# Milliways.net
KiCad netlist of a schematic drawn in EasyEDA Pro
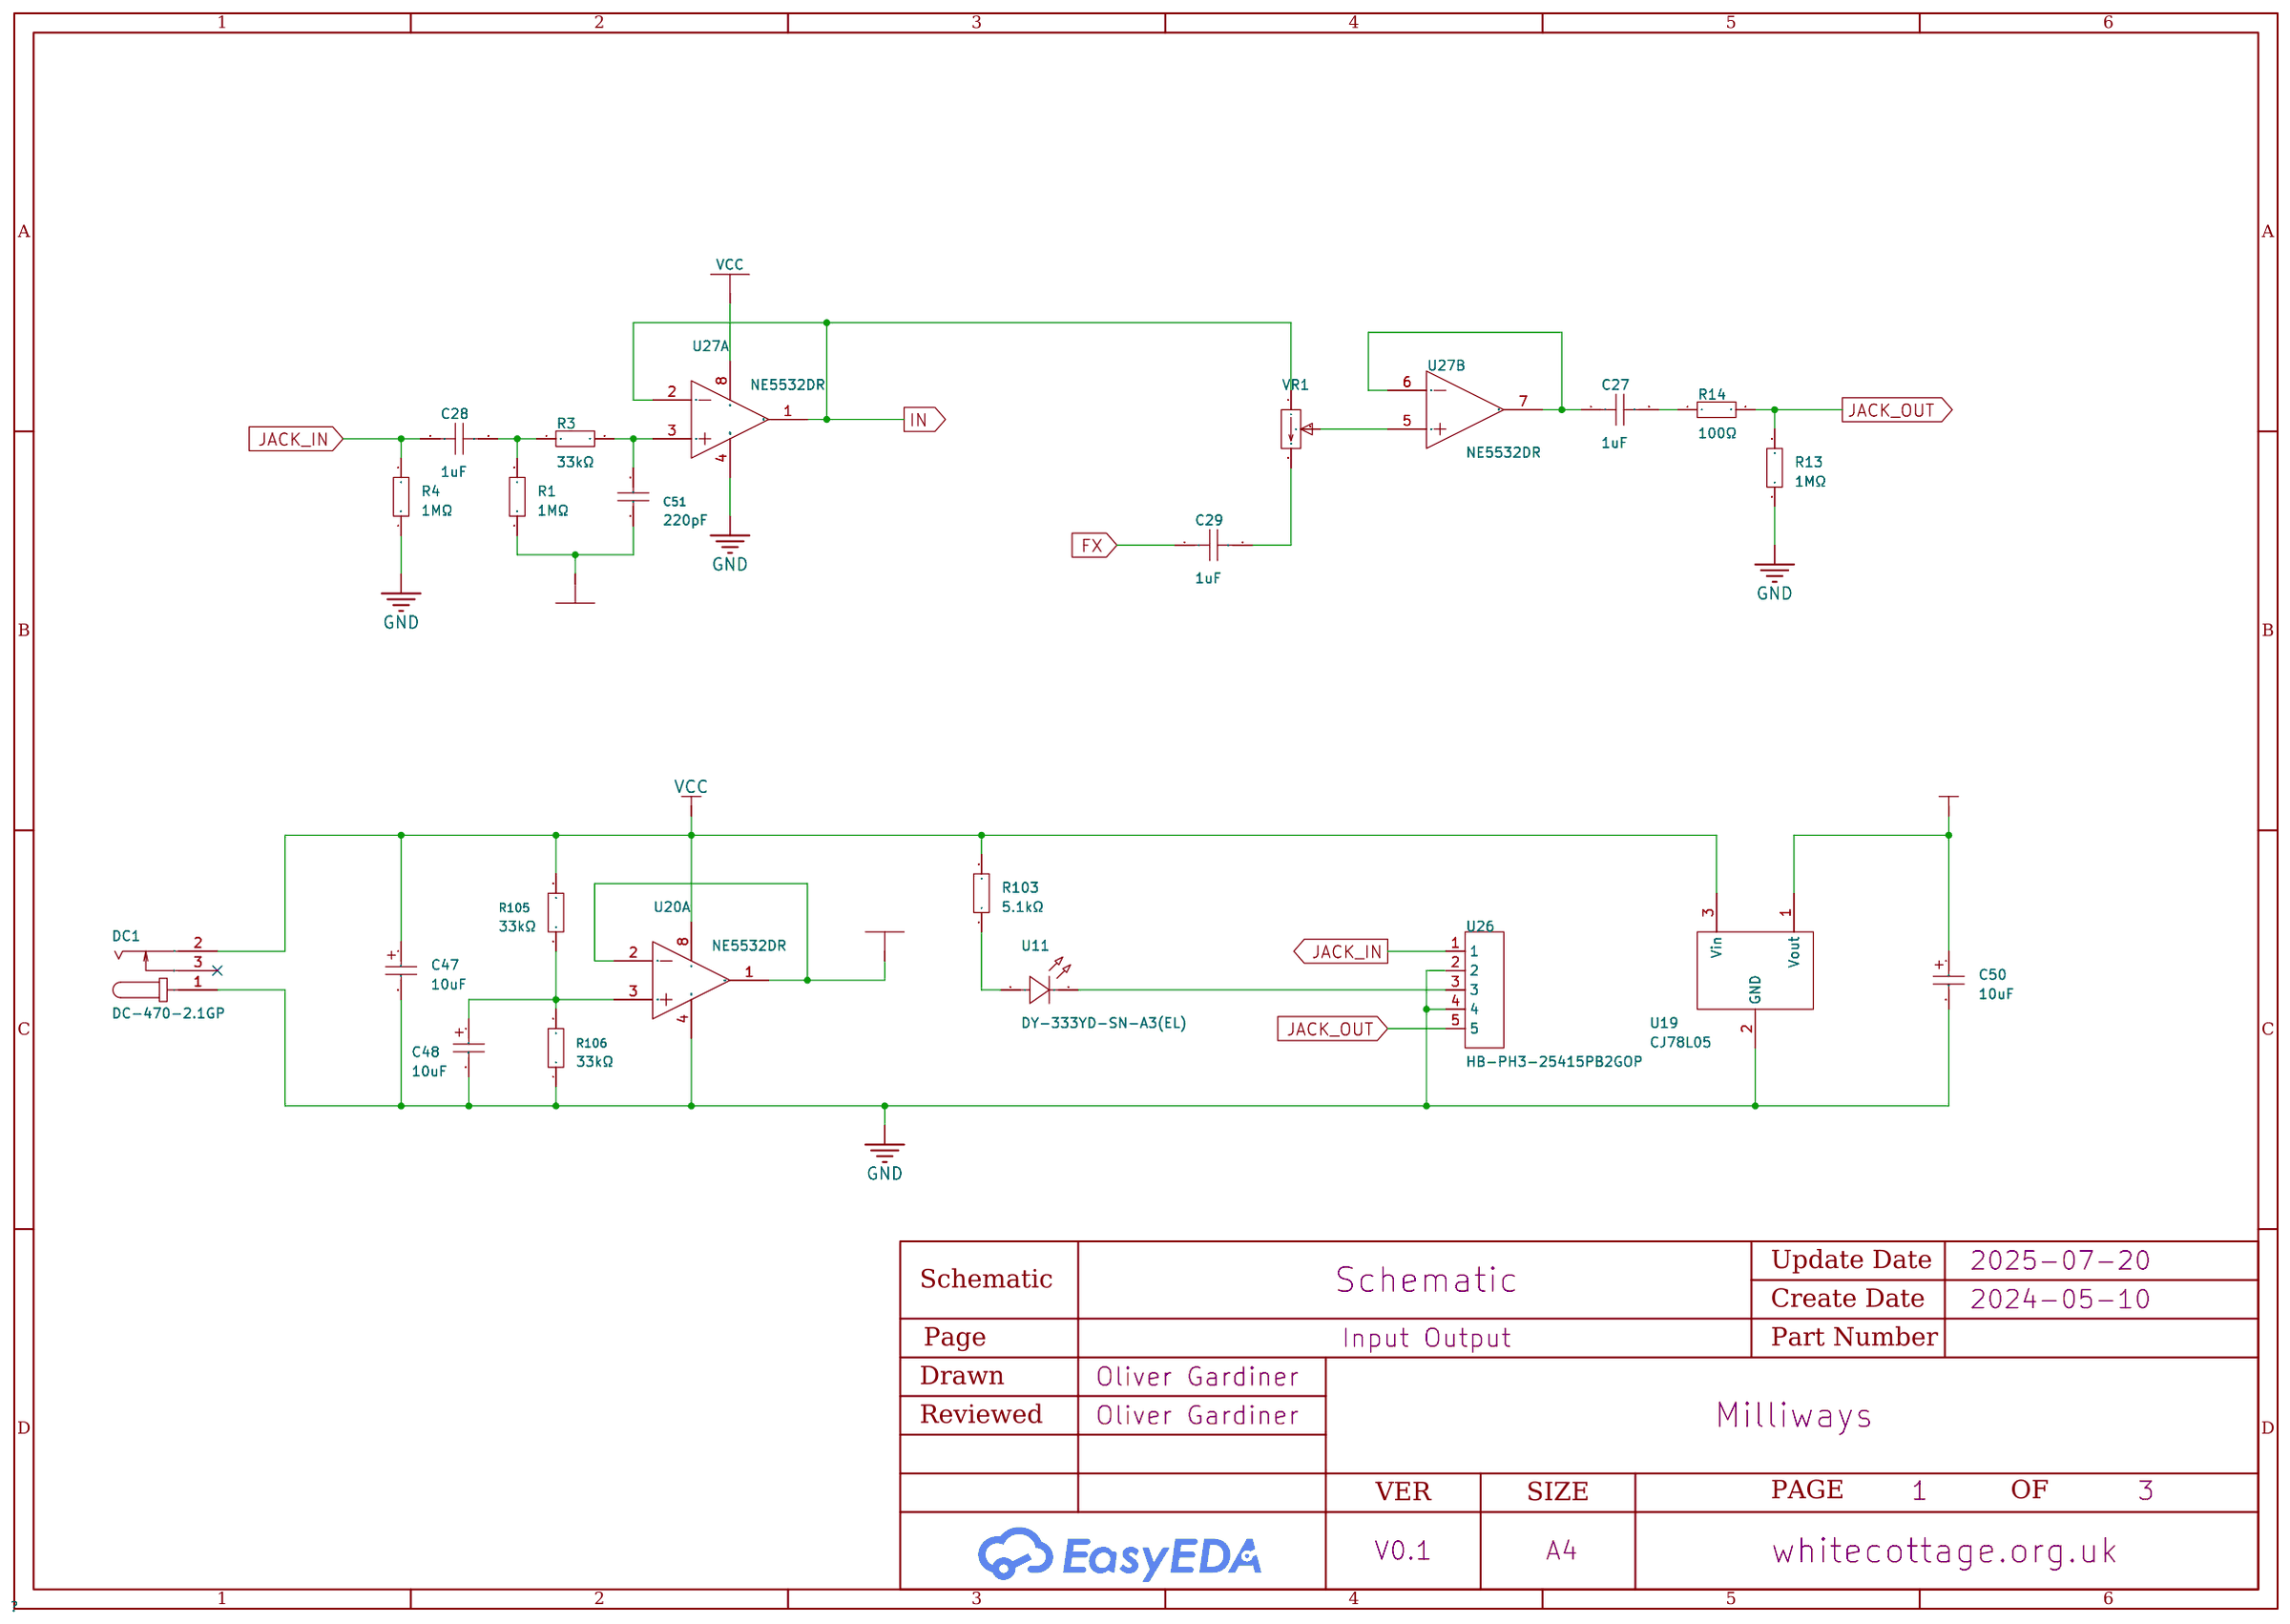
[diagram p0: Input Output]
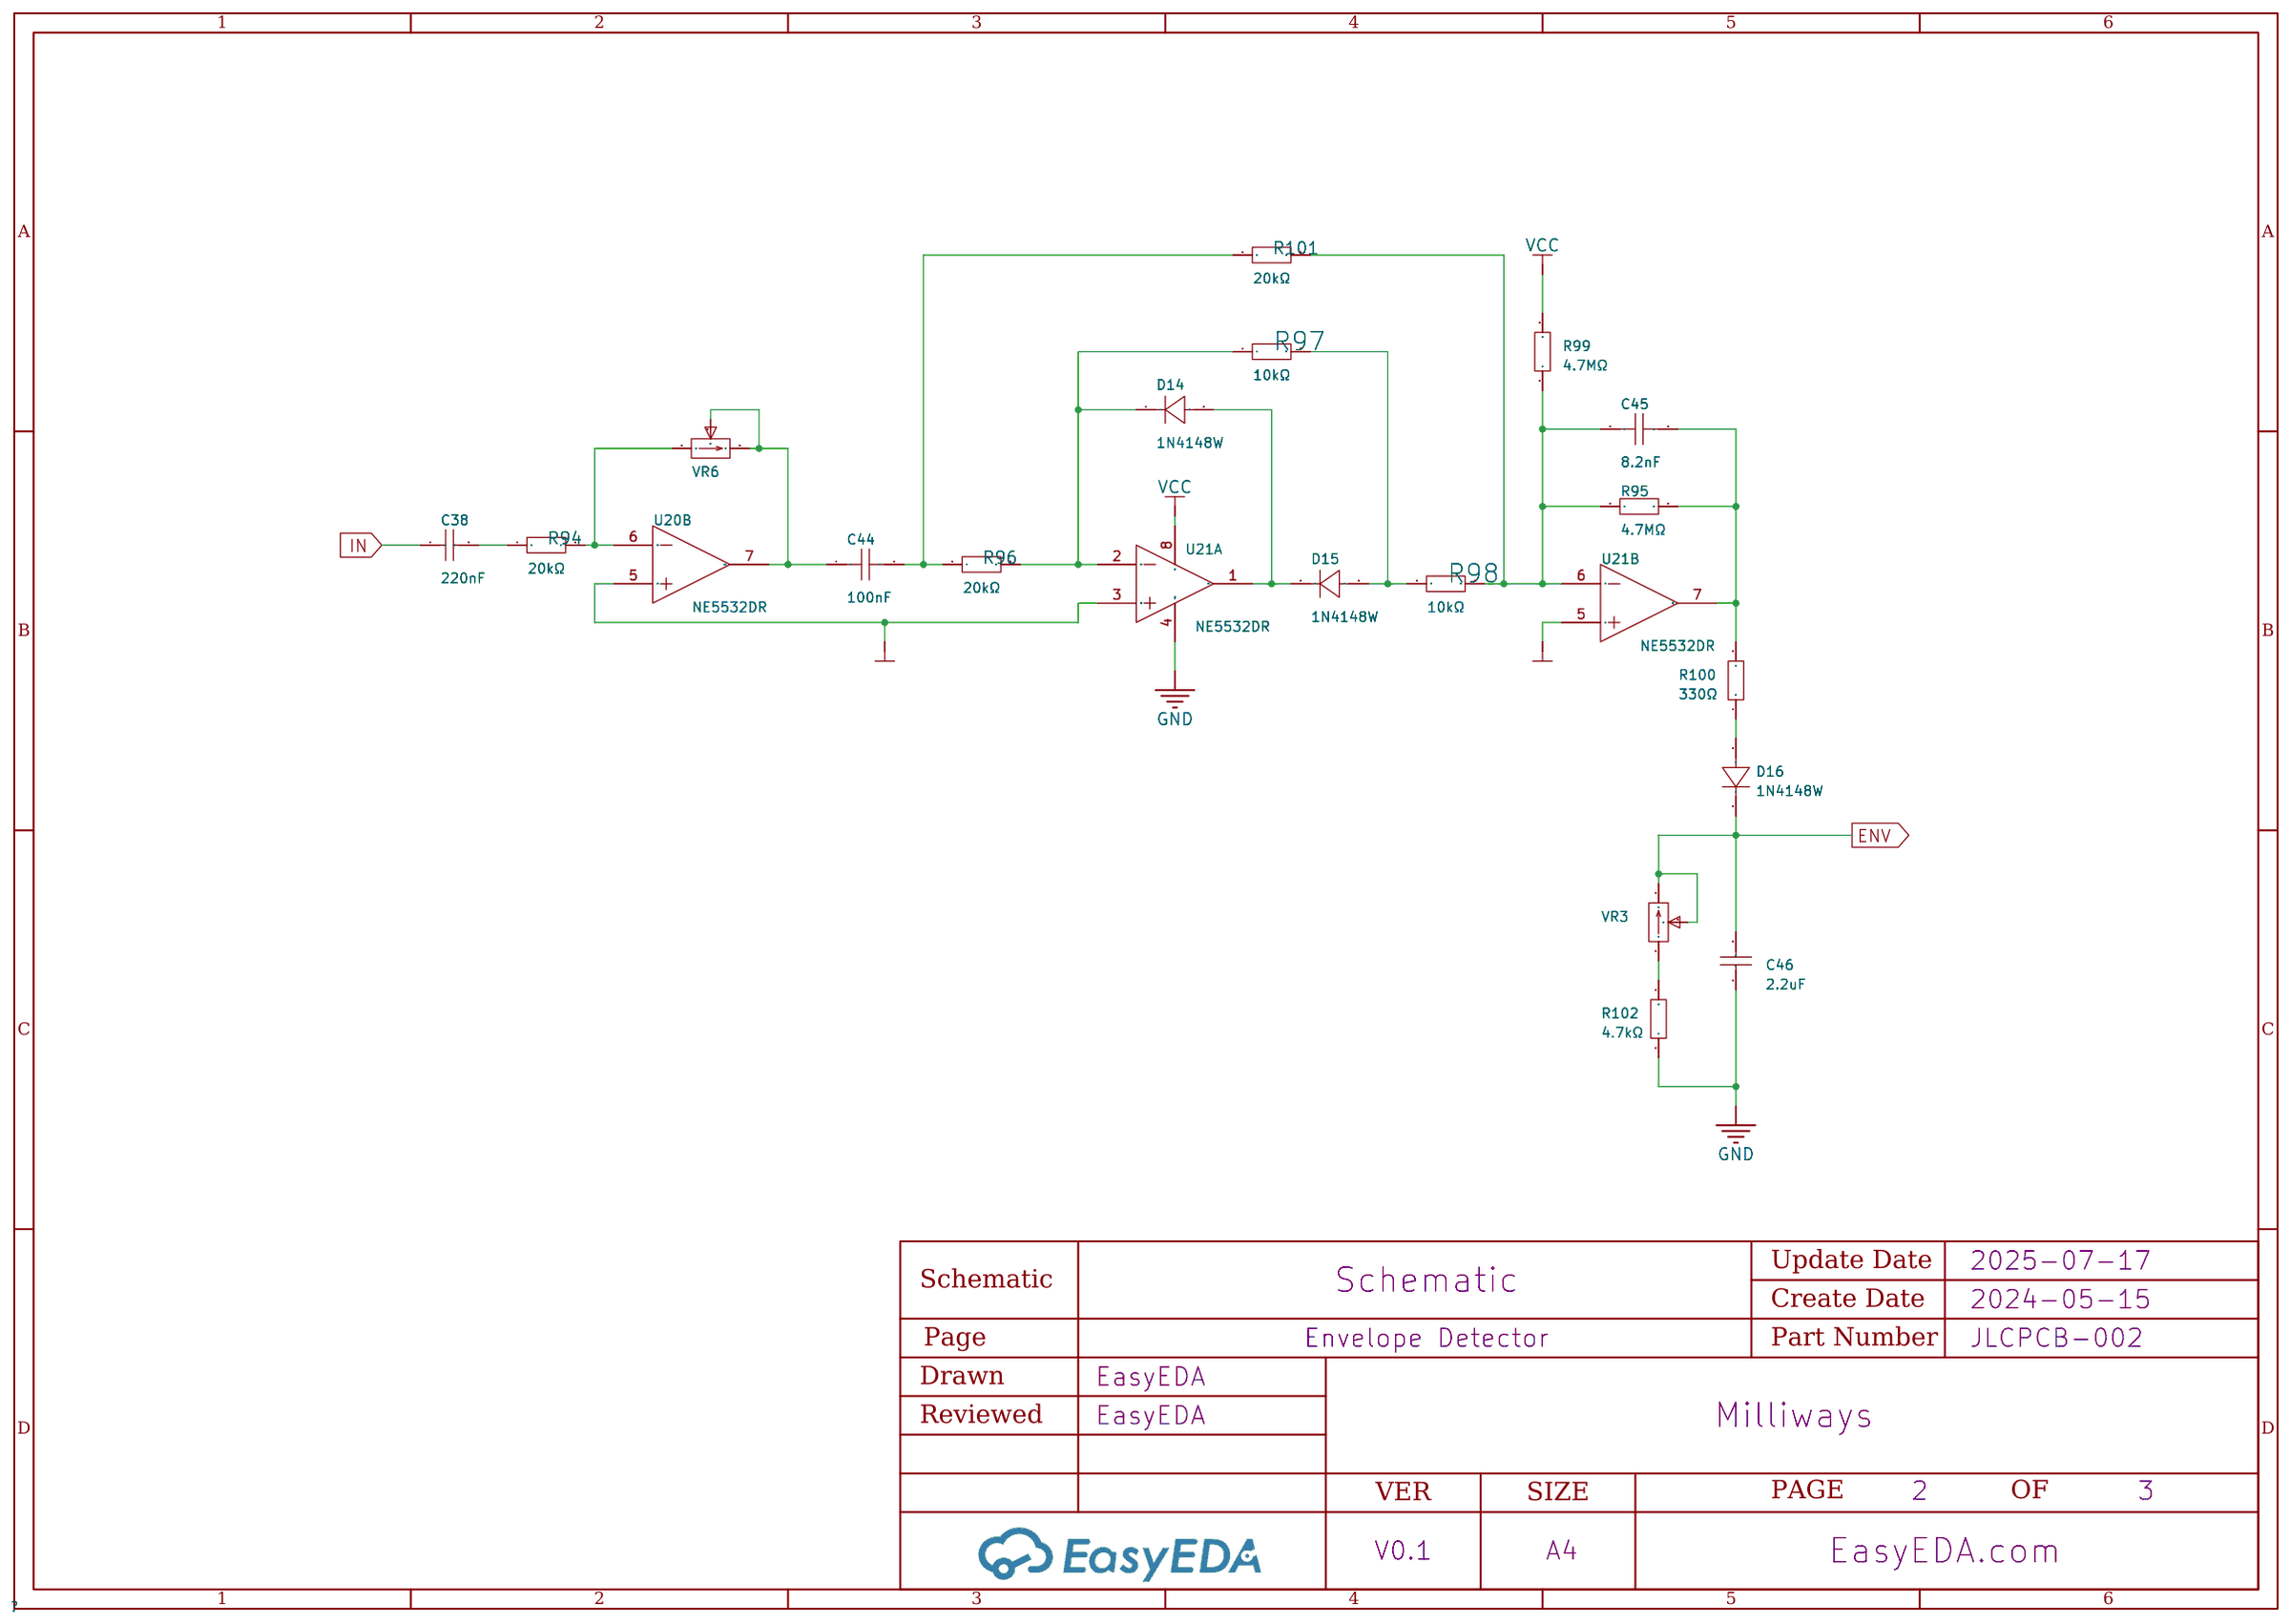
[diagram p1: Envelope Detector]
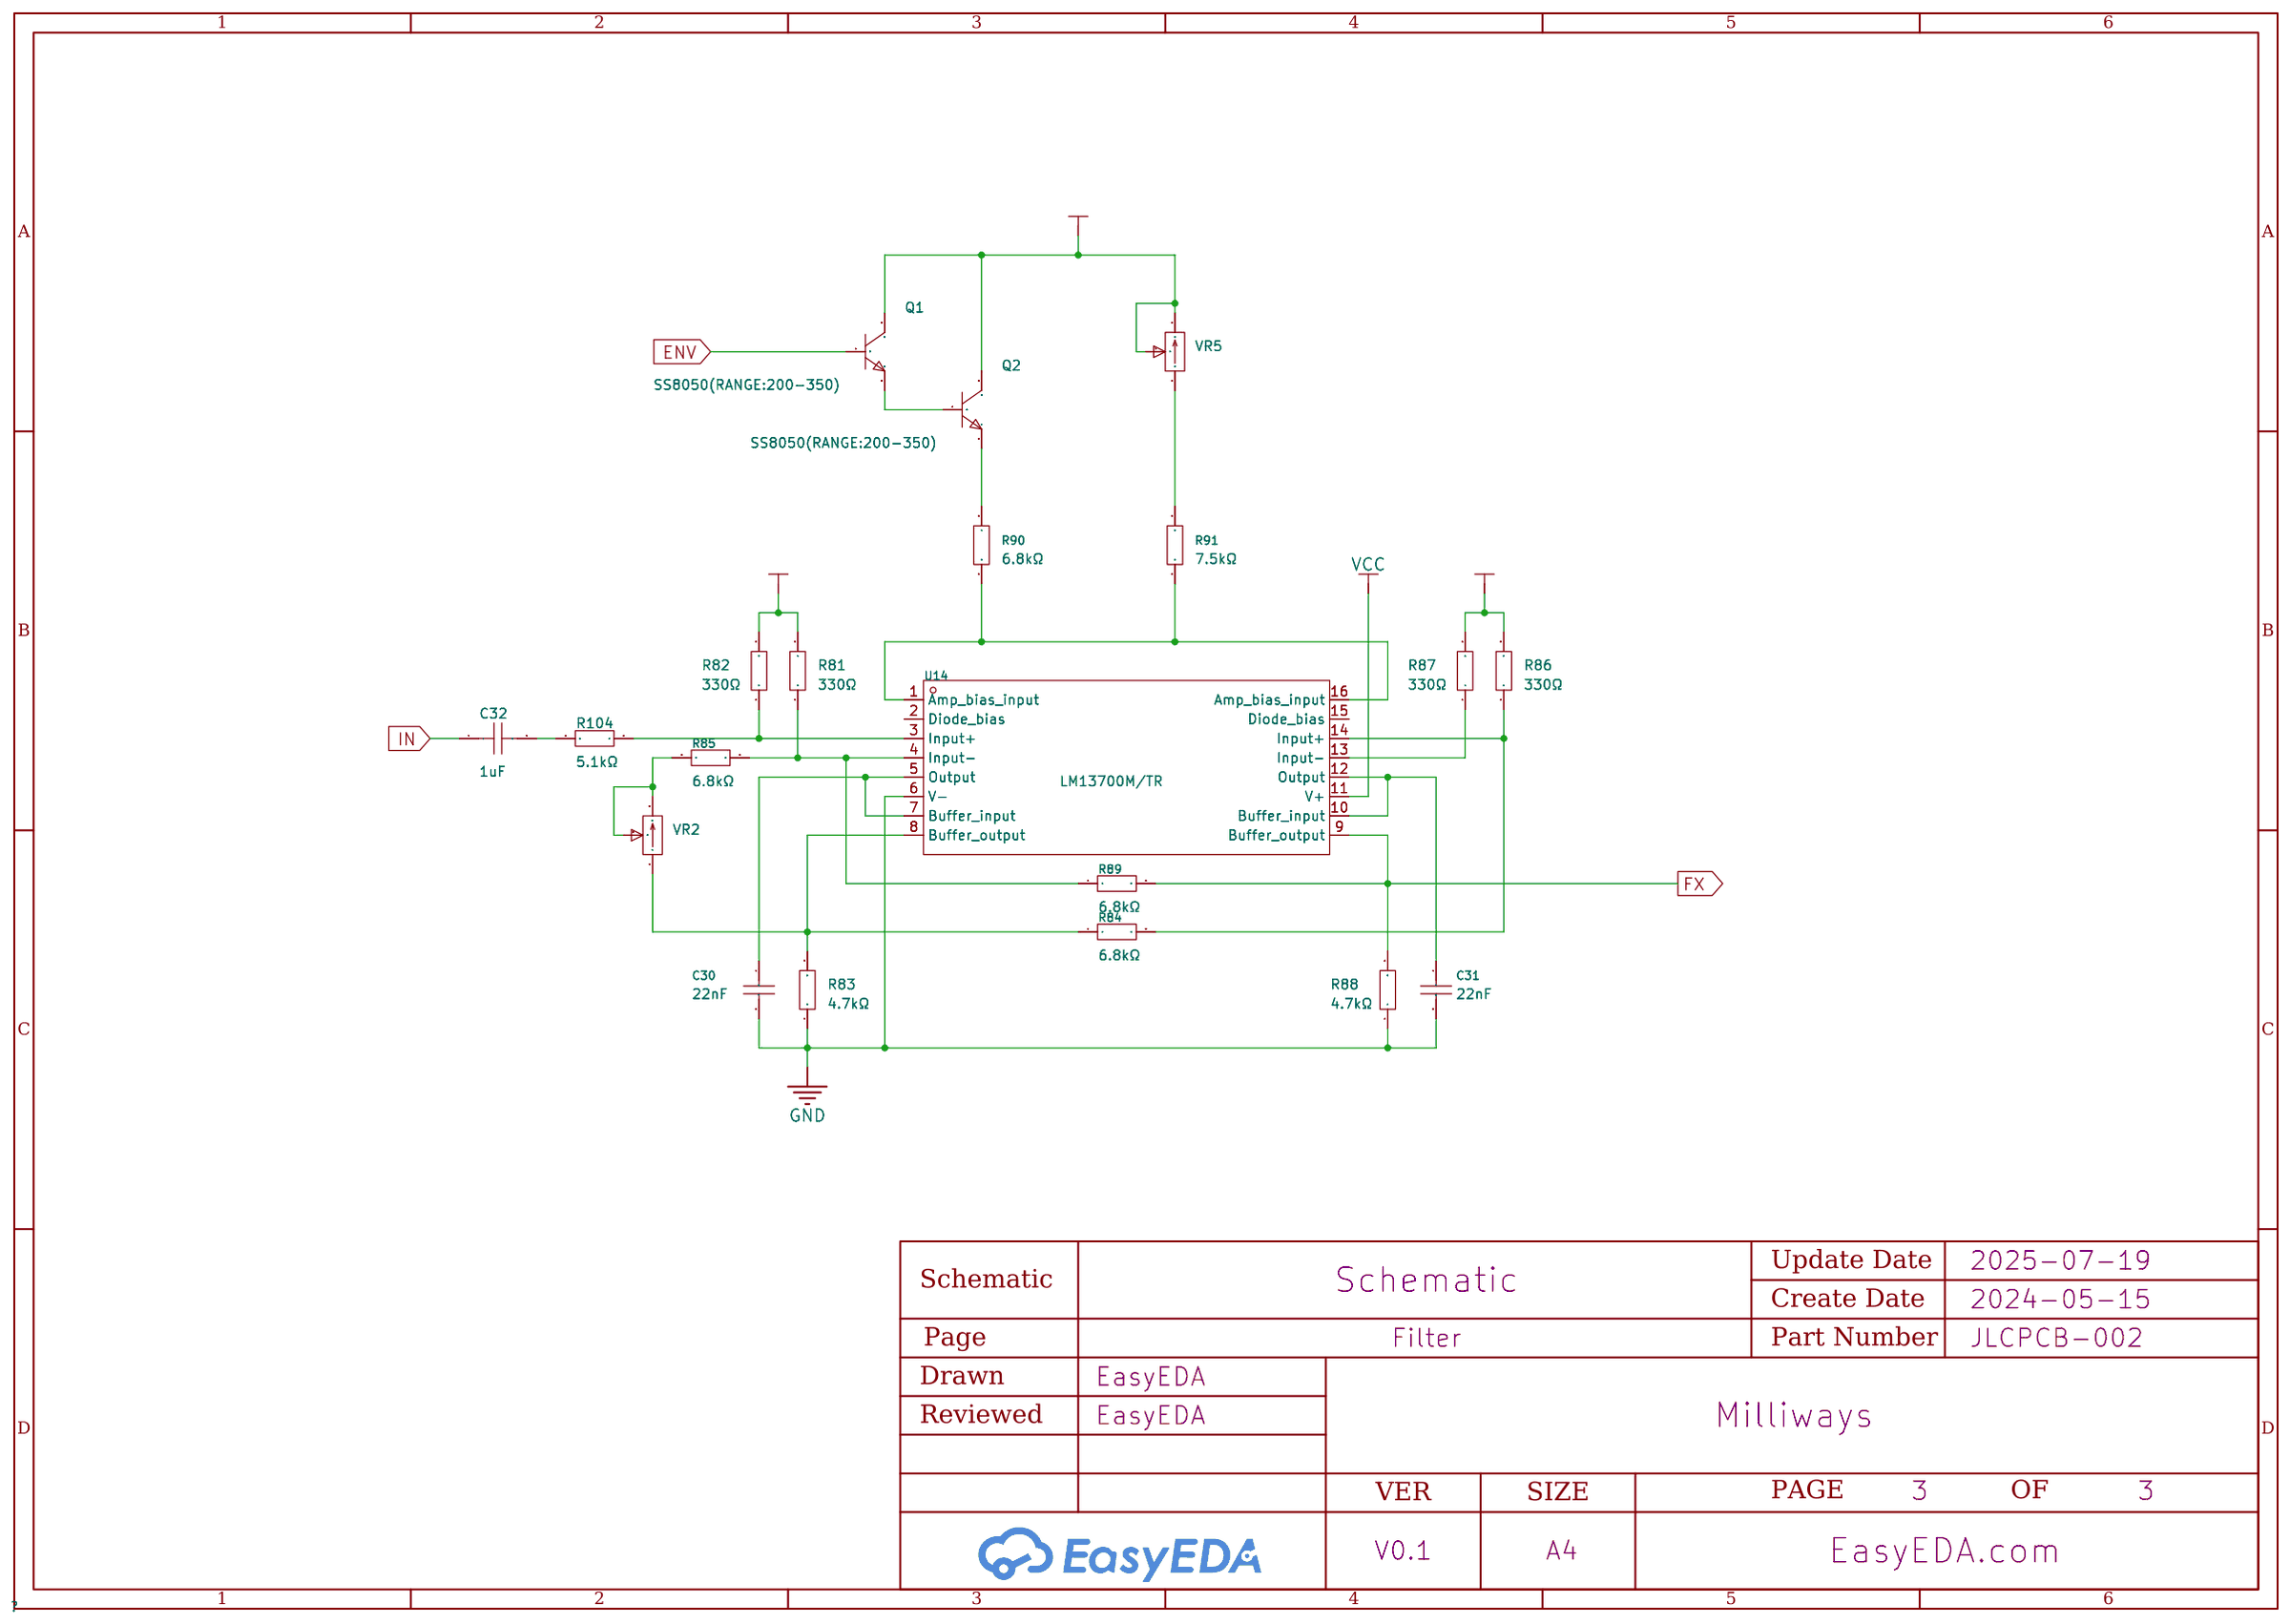
[diagram p2: Filter]

(export (version "E")
  (design (tool "Eeschema 10.0.6"))
  (components
    (comp (ref "C27")
      (value "1uF")
      (fields
        (field (name "Manufacturer Part") "CL10A105KB8NNNC")
        (field (name "Manufacturer") "SAMSUNG(三星)")
      )
      (libsource (lib "easyedapro") (part "CL10A105KB8NNNC"))
    )
    (comp (ref "C28")
      (value "1uF")
      (fields
        (field (name "Manufacturer Part") "CL10A105KB8NNNC")
        (field (name "Manufacturer") "SAMSUNG(三星)")
      )
      (libsource (lib "easyedapro") (part "CL10A105KB8NNNC"))
    )
    (comp (ref "C29")
      (value "1uF")
      (fields
        (field (name "Manufacturer Part") "CL10A105KB8NNNC")
        (field (name "Manufacturer") "SAMSUNG(三星)")
      )
      (libsource (lib "easyedapro") (part "CL10A105KB8NNNC"))
    )
    (comp (ref "C47")
      (value "10uF")
      (footprint "easyedapro:CAP-SMD_L3.2-W1.6-RD-C7171")
      (fields (field (name "Manufacturer Part") "TAJA106K016RNJ") (field (name "Manufacturer") "Kyocera AVX"))
      (libsource (lib "easyedapro") (part "TAJA106K016RNJ"))
    )
    (comp (ref "C48")
      (value "10uF")
      (footprint "easyedapro:CAP-SMD_L3.2-W1.6-RD-C7171")
      (fields (field (name "Manufacturer Part") "TAJA106K016RNJ") (field (name "Manufacturer") "Kyocera AVX"))
      (libsource (lib "easyedapro") (part "TAJA106K016RNJ"))
    )
    (comp (ref "C50")
      (value "10uF")
      (footprint "easyedapro:CAP-SMD_L3.2-W1.6-RD-C7171")
      (fields (field (name "Manufacturer Part") "TAJA106K016RNJ") (field (name "Manufacturer") "Kyocera AVX"))
      (libsource (lib "easyedapro") (part "TAJA106K016RNJ"))
    )
    (comp (ref "C51")
      (value "220pF")
      (footprint "easyedapro:C0603")
      (fields
        (field (name "Manufacturer Part") "CL10B221KB8NNNC")
        (field (name "Manufacturer") "SAMSUNG(三星)")
      )
      (libsource (lib "easyedapro") (part "CL10B221KB8NNNC"))
    )
    (comp (ref "DC1")
      (value "DC-470-2.1GP")
      (footprint "easyedapro:DC-IN-TH_DC-470-2.1GP")
      (fields (field (name "Manufacturer") "GANGYUAN(港源)"))
      (libsource (lib "easyedapro") (part "DC-470-2.1GP"))
    )
    (comp (ref "R1")
      (value "1MΩ")
      (footprint "easyedapro:R0603")
      (fields
        (field (name "Manufacturer Part") "0603WAF1004T5E")
        (field (name "Manufacturer") "UNI-ROYAL(厚声)")
      )
      (libsource (lib "easyedapro") (part "Res"))
    )
    (comp (ref "R3")
      (value "33kΩ")
      (footprint "easyedapro:R0603")
      (fields
        (field (name "Manufacturer Part") "0603WAF3302T5E")
        (field (name "Manufacturer") "UNI-ROYAL(厚声)")
      )
      (libsource (lib "easyedapro") (part "Res"))
    )
    (comp (ref "R4")
      (value "1MΩ")
      (footprint "easyedapro:R0603")
      (fields
        (field (name "Manufacturer Part") "0603WAF1004T5E")
        (field (name "Manufacturer") "UNI-ROYAL(厚声)")
      )
      (libsource (lib "easyedapro") (part "Res"))
    )
    (comp (ref "R13")
      (value "1MΩ")
      (footprint "easyedapro:R0603")
      (fields
        (field (name "Manufacturer Part") "0603WAF1004T5E")
        (field (name "Manufacturer") "UNI-ROYAL(厚声)")
      )
      (libsource (lib "easyedapro") (part "Res"))
    )
    (comp (ref "R14")
      (value "100Ω")
      (footprint "easyedapro:R0603")
      (fields
        (field (name "Manufacturer Part") "0603WAF1000T5E")
        (field (name "Manufacturer") "UNI-ROYAL(厚声)")
      )
      (libsource (lib "easyedapro") (part "Res"))
    )
    (comp (ref "R103")
      (value "5.1kΩ")
      (footprint "easyedapro:R0603")
      (fields
        (field (name "Manufacturer Part") "0603WAF5101T5E")
        (field (name "Manufacturer") "UNI-ROYAL(厚声)")
      )
      (libsource (lib "easyedapro") (part "0603WAF5101T5E"))
    )
    (comp (ref "R105")
      (value "33kΩ")
      (footprint "easyedapro:R0603")
      (fields
        (field (name "Manufacturer Part") "0603WAF3302T5E")
        (field (name "Manufacturer") "UNI-ROYAL(厚声)")
      )
      (libsource (lib "easyedapro") (part "0603WAF3302T5E"))
    )
    (comp (ref "R106")
      (value "33kΩ")
      (footprint "easyedapro:R0603")
      (fields
        (field (name "Manufacturer Part") "0603WAF3302T5E")
        (field (name "Manufacturer") "UNI-ROYAL(厚声)")
      )
      (libsource (lib "easyedapro") (part "0603WAF3302T5E"))
    )
    (comp (ref "U11")
      (value "DY-333YD-SN-A3(EL)")
      (footprint "easyedapro:LED-TH_BD5.0-P2.54-FD-1")
      (fields (field (name "Manufacturer") "TONYU(东裕)"))
      (libsource (lib "easyedapro") (part "DY-333YD-SN-A3(EL)"))
    )
    (comp (ref "U19")
      (value "CJ78L05")
      (footprint "easyedapro:SOT-89-3_L4.5-W2.5-P1.50-LS4.2-BR")
      (fields (field (name "Manufacturer") "CJ(江苏长电/长晶)"))
      (libsource (lib "easyedapro") (part "CJ78L05"))
    )
    (comp (ref "U20")
      (value "NE5532DR")
      (footprint "easyedapro:SOIC-8_L4.9-W3.9-P1.27-LS6.0-BL")
      (fields (field (name "Manufacturer") "TI(德州仪器)"))
      (libsource (lib "easyedapro") (part "NE5532DR"))
    )
    (comp (ref "U26")
      (value "HB-PH3-25415PB2GOP")
      (footprint "easyedapro:HDR-TH_5P-P2.54-V-M")
      (fields (field (name "Manufacturer") "HANBO(汉博)"))
      (libsource (lib "easyedapro") (part "HB-PH3-25415PB2GOP"))
    )
    (comp (ref "U27")
      (value "NE5532DR")
      (footprint "easyedapro:SOIC-8_L4.9-W3.9-P1.27-LS6.0-BL")
      (fields (field (name "Manufacturer") "TI(德州仪器)"))
      (libsource (lib "easyedapro") (part "NE5532DR"))
    )
    (comp (ref "VR1")
      (value "~")
      (footprint "easyedapro:RD901F")
      (libsource (lib "easyedapro") (part "RD901F"))
    )
    (comp (ref "C38")
      (value "220nF")
      (footprint "easyedapro:C0603")
      (fields
        (field (name "Manufacturer Part") "CL10B224KA8NNNC")
        (field (name "Manufacturer") "SAMSUNG(三星)")
      )
      (libsource (lib "easyedapro") (part "CL10B224KA8NNNC"))
    )
    (comp (ref "C44")
      (value "100nF")
      (footprint "easyedapro:C0603")
      (fields
        (field (name "Manufacturer Part") "CC0603KRX7R9BB104")
        (field (name "Manufacturer") "YAGEO(国巨)")
      )
      (libsource (lib "easyedapro") (part "CC0603KRX7R9BB104"))
    )
    (comp (ref "C45")
      (value "8.2nF")
      (footprint "easyedapro:C0603")
      (description "Capacitance:8.2nF Tolerance:±10% Tolerance:±10% Voltage Rating:50V Temperature Coefficient:X7R")
      (fields (field (name "Manufacturer Part") "0603B822K500NT") (field (name "Manufacturer") "FH(风华)"))
      (libsource (lib "easyedapro") (part "0603B822K500NT"))
    )
    (comp (ref "C46")
      (value "2.2uF")
      (footprint "easyedapro:C0603")
      (fields
        (field (name "Manufacturer Part") "CL10A225KO8NNNC")
        (field (name "Manufacturer") "SAMSUNG(三星)")
      )
      (libsource (lib "easyedapro") (part "CL10A225KO8NNNC"))
    )
    (comp (ref "D14")
      (value "1N4148W")
      (fields (field (name "Manufacturer") "ST(先科)"))
      (libsource (lib "easyedapro") (part "d_1n4007"))
    )
    (comp (ref "D15")
      (value "1N4148W")
      (fields (field (name "Manufacturer") "ST(先科)"))
      (libsource (lib "easyedapro") (part "d_1n4007"))
    )
    (comp (ref "D16")
      (value "1N4148W")
      (fields (field (name "Manufacturer") "ST(先科)"))
      (libsource (lib "easyedapro") (part "d_1n4007"))
    )
    (comp (ref "R94")
      (value "20kΩ")
      (footprint "easyedapro:R0603")
      (fields
        (field (name "Manufacturer Part") "0603WAF2002T5E")
        (field (name "Manufacturer") "UNI-ROYAL(厚声)")
      )
      (libsource (lib "easyedapro") (part "0603WAF2002T5E"))
    )
    (comp (ref "R95")
      (value "4.7MΩ")
      (footprint "easyedapro:R0603")
      (fields
        (field (name "Manufacturer Part") "0603WAF4704T5E")
        (field (name "Manufacturer") "UNI-ROYAL(厚声)")
      )
      (libsource (lib "easyedapro") (part "0603WAF4704T5E"))
    )
    (comp (ref "R96")
      (value "20kΩ")
      (footprint "easyedapro:R0603")
      (fields
        (field (name "Manufacturer Part") "0603WAF2002T5E")
        (field (name "Manufacturer") "UNI-ROYAL(厚声)")
      )
      (libsource (lib "easyedapro") (part "0603WAF2002T5E"))
    )
    (comp (ref "R97")
      (value "10kΩ")
      (footprint "easyedapro:R0603")
      (fields
        (field (name "Manufacturer Part") "0603WAF1002T5E")
        (field (name "Manufacturer") "UNI-ROYAL(厚声)")
      )
      (libsource (lib "easyedapro") (part "0603WAF1002T5E"))
    )
    (comp (ref "R98")
      (value "10kΩ")
      (footprint "easyedapro:R0603")
      (fields
        (field (name "Manufacturer Part") "0603WAF1002T5E")
        (field (name "Manufacturer") "UNI-ROYAL(厚声)")
      )
      (libsource (lib "easyedapro") (part "0603WAF1002T5E"))
    )
    (comp (ref "R99")
      (value "4.7MΩ")
      (footprint "easyedapro:R0603")
      (fields
        (field (name "Manufacturer Part") "0603WAF4704T5E")
        (field (name "Manufacturer") "UNI-ROYAL(厚声)")
      )
      (libsource (lib "easyedapro") (part "0603WAF4704T5E"))
    )
    (comp (ref "R100")
      (value "330Ω")
      (footprint "easyedapro:R0603")
      (fields
        (field (name "Manufacturer Part") "0603WAF3300T5E")
        (field (name "Manufacturer") "UNI-ROYAL(厚声)")
      )
      (libsource (lib "easyedapro") (part "0603WAF3300T5E"))
    )
    (comp (ref "R101")
      (value "20kΩ")
      (footprint "easyedapro:R0603")
      (fields
        (field (name "Manufacturer Part") "0603WAF2002T5E")
        (field (name "Manufacturer") "UNI-ROYAL(厚声)")
      )
      (libsource (lib "easyedapro") (part "0603WAF2002T5E"))
    )
    (comp (ref "R102")
      (value "4.7kΩ")
      (footprint "easyedapro:R0603")
      (fields
        (field (name "Manufacturer Part") "0603WAF4701T5E")
        (field (name "Manufacturer") "UNI-ROYAL(厚声)")
      )
      (libsource (lib "easyedapro") (part "0603WAF4701T5E"))
    )
    (comp (ref "U21")
      (value "NE5532DR")
      (footprint "easyedapro:SOIC-8_L4.9-W3.9-P1.27-LS6.0-BL")
      (fields (field (name "Manufacturer") "TI(德州仪器)"))
      (libsource (lib "easyedapro") (part "NE5532DR"))
    )
    (comp (ref "VR3")
      (value "~")
      (footprint "easyedapro:RD901F")
      (libsource (lib "easyedapro") (part "RD901F"))
    )
    (comp (ref "VR6")
      (value "~")
      (footprint "easyedapro:RD901F")
      (libsource (lib "easyedapro") (part "RD901F"))
    )
    (comp (ref "C30")
      (value "22nF")
      (footprint "easyedapro:C0603")
      (fields
        (field (name "Manufacturer Part") "CL10B223KB8NNNC")
        (field (name "Manufacturer") "SAMSUNG(三星)")
      )
      (libsource (lib "easyedapro") (part "CL10B223KB8NNNC"))
    )
    (comp (ref "C31")
      (value "22nF")
      (footprint "easyedapro:C0603")
      (fields
        (field (name "Manufacturer Part") "CL10B223KB8NNNC")
        (field (name "Manufacturer") "SAMSUNG(三星)")
      )
      (libsource (lib "easyedapro") (part "CL10B223KB8NNNC"))
    )
    (comp (ref "C32")
      (value "1uF")
      (footprint "easyedapro:C0603")
      (fields
        (field (name "Manufacturer Part") "CL10A105KB8NNNC")
        (field (name "Manufacturer") "SAMSUNG(三星)")
      )
      (libsource (lib "easyedapro") (part "CL10A105KB8NNNC"))
    )
    (comp (ref "Q1")
      (value "SS8050(RANGE:200-350)")
      (footprint "easyedapro:SOT-23-3_L2.9-W1.3-P1.90-LS2.4-BR")
      (fields (field (name "Manufacturer") "CJ(江苏长电/长晶)"))
      (libsource (lib "easyedapro") (part "SS8050_C2150"))
    )
    (comp (ref "Q2")
      (value "SS8050(RANGE:200-350)")
      (footprint "easyedapro:SOT-23-3_L2.9-W1.3-P1.90-LS2.4-BR")
      (fields (field (name "Manufacturer") "CJ(江苏长电/长晶)"))
      (libsource (lib "easyedapro") (part "SS8050_C2150"))
    )
    (comp (ref "R81")
      (value "330Ω")
      (footprint "easyedapro:R0603")
      (fields
        (field (name "Manufacturer Part") "0603WAF3300T5E")
        (field (name "Manufacturer") "UNI-ROYAL(厚声)")
      )
      (libsource (lib "easyedapro") (part "0603WAF3300T5E"))
    )
    (comp (ref "R82")
      (value "330Ω")
      (footprint "easyedapro:R0603")
      (fields
        (field (name "Manufacturer Part") "0603WAF3300T5E")
        (field (name "Manufacturer") "UNI-ROYAL(厚声)")
      )
      (libsource (lib "easyedapro") (part "0603WAF3300T5E"))
    )
    (comp (ref "R83")
      (value "4.7kΩ")
      (footprint "easyedapro:R0603")
      (fields
        (field (name "Manufacturer Part") "0603WAF4701T5E")
        (field (name "Manufacturer") "UNI-ROYAL(厚声)")
      )
      (libsource (lib "easyedapro") (part "0603WAF4701T5E"))
    )
    (comp (ref "R84")
      (value "6.8kΩ")
      (footprint "easyedapro:R0603")
      (fields
        (field (name "Manufacturer Part") "0603WAF6801T5E")
        (field (name "Manufacturer") "UNI-ROYAL(厚声)")
      )
      (libsource (lib "easyedapro") (part "0603WAF6801T5E"))
    )
    (comp (ref "R85")
      (value "6.8kΩ")
      (footprint "easyedapro:R0603")
      (fields
        (field (name "Manufacturer Part") "0603WAF6801T5E")
        (field (name "Manufacturer") "UNI-ROYAL(厚声)")
      )
      (libsource (lib "easyedapro") (part "0603WAF6801T5E"))
    )
    (comp (ref "R86")
      (value "330Ω")
      (footprint "easyedapro:R0603")
      (fields
        (field (name "Manufacturer Part") "0603WAF3300T5E")
        (field (name "Manufacturer") "UNI-ROYAL(厚声)")
      )
      (libsource (lib "easyedapro") (part "0603WAF3300T5E"))
    )
    (comp (ref "R87")
      (value "330Ω")
      (footprint "easyedapro:R0603")
      (fields
        (field (name "Manufacturer Part") "0603WAF3300T5E")
        (field (name "Manufacturer") "UNI-ROYAL(厚声)")
      )
      (libsource (lib "easyedapro") (part "0603WAF3300T5E"))
    )
    (comp (ref "R88")
      (value "4.7kΩ")
      (footprint "easyedapro:R0603")
      (fields
        (field (name "Manufacturer Part") "0603WAF4701T5E")
        (field (name "Manufacturer") "UNI-ROYAL(厚声)")
      )
      (libsource (lib "easyedapro") (part "0603WAF4701T5E"))
    )
    (comp (ref "R89")
      (value "6.8kΩ")
      (footprint "easyedapro:R0603")
      (fields
        (field (name "Manufacturer Part") "0603WAF6801T5E")
        (field (name "Manufacturer") "UNI-ROYAL(厚声)")
      )
      (libsource (lib "easyedapro") (part "0603WAF6801T5E"))
    )
    (comp (ref "R90")
      (value "6.8kΩ")
      (footprint "easyedapro:R0603")
      (fields
        (field (name "Manufacturer Part") "0603WAF6801T5E")
        (field (name "Manufacturer") "UNI-ROYAL(厚声)")
      )
      (libsource (lib "easyedapro") (part "0603WAF6801T5E"))
    )
    (comp (ref "R91")
      (value "7.5kΩ")
      (footprint "easyedapro:R0603")
      (fields
        (field (name "Manufacturer Part") "0603WAF7501T5E")
        (field (name "Manufacturer") "UNI-ROYAL(厚声)")
      )
      (libsource (lib "easyedapro") (part "0603WAF7501T5E"))
    )
    (comp (ref "R104")
      (value "5.1kΩ")
      (footprint "easyedapro:R0603")
      (fields
        (field (name "Manufacturer Part") "0603WAF5101T5E")
        (field (name "Manufacturer") "UNI-ROYAL(厚声)")
      )
      (libsource (lib "easyedapro") (part "0603WAF5101T5E"))
    )
    (comp (ref "U14")
      (value "LM13700M/TR")
      (footprint "easyedapro:SOP-16_L9.9-W3.9-P1.27-LS6.0-BL")
      (fields (field (name "Manufacturer") "HGSEMI(华冠)"))
      (libsource (lib "easyedapro") (part "LM13700M/TR"))
    )
    (comp (ref "VR2")
      (value "~")
      (footprint "easyedapro:RD901F")
      (libsource (lib "easyedapro") (part "RD901F"))
    )
    (comp (ref "VR5")
      (value "~")
      (footprint "easyedapro:RD901F")
      (libsource (lib "easyedapro") (part "RD901F"))
    )
  )
  (nets
    (net (code "1") (name "+5V") (class "Default")
      (node (ref "C50") (pin "1") (pinfunction "1_1") (pintype "input"))
      (node (ref "Q1") (pin "3") (pinfunction "C_3") (pintype "unspecified"))
      (node (ref "Q2") (pin "3") (pinfunction "C_3") (pintype "unspecified"))
      (node (ref "U19") (pin "1") (pinfunction "Vout_1") (pintype "unspecified"))
      (node (ref "VR5") (pin "2") (pinfunction "2_2") (pintype "input"))
      (node (ref "VR5") (pin "3") (pinfunction "3_3") (pintype "input"))
    )
    (net (code "2") (name "ENV") (class "Default")
      (node (ref "C46") (pin "2") (pinfunction "2_2") (pintype "input"))
      (node (ref "D16") (pin "1") (pinfunction "K_1") (pintype "input"))
      (node (ref "Q1") (pin "1") (pinfunction "B_1") (pintype "unspecified"))
      (node (ref "VR3") (pin "2") (pinfunction "2_2") (pintype "input"))
      (node (ref "VR3") (pin "3") (pinfunction "3_3") (pintype "input"))
    )
    (net (code "3") (name "FX") (class "Default")
      (node (ref "C29") (pin "1") (pinfunction "1_1") (pintype "unspecified"))
      (node (ref "R88") (pin "2") (pinfunction "2_2") (pintype "input"))
      (node (ref "R89") (pin "2") (pinfunction "2_2") (pintype "input"))
      (node (ref "U14") (pin "9") (pinfunction "Buffer_output_9") (pintype "input"))
    )
    (net (code "4") (name "GND") (class "Default")
      (node (ref "C30") (pin "2") (pinfunction "2_2") (pintype "input"))
      (node (ref "C31") (pin "2") (pinfunction "2_2") (pintype "input"))
      (node (ref "C46") (pin "1") (pinfunction "1_1") (pintype "input"))
      (node (ref "C47") (pin "2") (pinfunction "2_2") (pintype "input"))
      (node (ref "C48") (pin "2") (pinfunction "2_2") (pintype "input"))
      (node (ref "C50") (pin "2") (pinfunction "2_2") (pintype "input"))
      (node (ref "DC1") (pin "1") (pinfunction "1_1") (pintype "unspecified"))
      (node (ref "R102") (pin "1") (pinfunction "1_1") (pintype "input"))
      (node (ref "R106") (pin "1") (pinfunction "1_1") (pintype "input"))
      (node (ref "R13") (pin "1") (pinfunction "1_1") (pintype "input"))
      (node (ref "R4") (pin "1") (pinfunction "1_1") (pintype "input"))
      (node (ref "R83") (pin "1") (pinfunction "1_1") (pintype "input"))
      (node (ref "R88") (pin "1") (pinfunction "1_1") (pintype "input"))
      (node (ref "U14") (pin "6") (pinfunction "V-_6") (pintype "input"))
      (node (ref "U19") (pin "2") (pinfunction "GND_2") (pintype "unspecified"))
      (node (ref "U20") (pin "4") (pinfunction "VCC-/GND_4") (pintype "unspecified"))
      (node (ref "U21") (pin "4") (pinfunction "VCC-/GND_4") (pintype "unspecified"))
      (node (ref "U26") (pin "2") (pinfunction "2_2") (pintype "unspecified"))
      (node (ref "U26") (pin "4") (pinfunction "4_4") (pintype "unspecified"))
      (node (ref "U27") (pin "4") (pinfunction "VCC-/GND_4") (pintype "unspecified"))
    )
    (net (code "5") (name "IN") (class "Default")
      (node (ref "C32") (pin "1") (pinfunction "1_1") (pintype "unspecified"))
      (node (ref "C38") (pin "1") (pinfunction "1_1") (pintype "input"))
      (node (ref "U27") (pin "1") (pinfunction "OUT1_1") (pintype "output"))
      (node (ref "U27") (pin "2") (pinfunction "IN1-_2") (pintype "unspecified"))
      (node (ref "VR1") (pin "1") (pinfunction "1_1") (pintype "input"))
    )
    (net (code "6") (name "JACK_IN") (class "Default")
      (node (ref "C28") (pin "1") (pinfunction "1_1") (pintype "unspecified"))
      (node (ref "R4") (pin "2") (pinfunction "2_2") (pintype "input"))
      (node (ref "U26") (pin "1") (pinfunction "1_1") (pintype "unspecified"))
    )
    (net (code "7") (name "JACK_OUT") (class "Default")
      (node (ref "R13") (pin "2") (pinfunction "2_2") (pintype "input"))
      (node (ref "R14") (pin "2") (pinfunction "2_2") (pintype "input"))
      (node (ref "U26") (pin "5") (pinfunction "5_5") (pintype "unspecified"))
    )
    (net (code "8") (name "Net-(C27-Pad2)") (class "Default")
      (node (ref "C27") (pin "2") (pinfunction "2_2") (pintype "unspecified"))
      (node (ref "R14") (pin "1") (pinfunction "1_1") (pintype "input"))
    )
    (net (code "9") (name "Net-(C28-Pad2)") (class "Default")
      (node (ref "C28") (pin "2") (pinfunction "2_2") (pintype "unspecified"))
      (node (ref "R1") (pin "2") (pinfunction "2_2") (pintype "input"))
      (node (ref "R3") (pin "1") (pinfunction "1_1") (pintype "input"))
    )
    (net (code "10") (name "Net-(C29-Pad2)") (class "Default")
      (node (ref "C29") (pin "2") (pinfunction "2_2") (pintype "unspecified"))
      (node (ref "VR1") (pin "3") (pinfunction "3_3") (pintype "input"))
    )
    (net (code "11") (name "Net-(C30-Pad1)") (class "Default")
      (node (ref "C30") (pin "1") (pinfunction "1_1") (pintype "input"))
      (node (ref "U14") (pin "5") (pinfunction "Output_5") (pintype "input"))
      (node (ref "U14") (pin "7") (pinfunction "Buffer_input_7") (pintype "input"))
    )
    (net (code "12") (name "Net-(C31-Pad1)") (class "Default")
      (node (ref "C31") (pin "1") (pinfunction "1_1") (pintype "input"))
      (node (ref "U14") (pin "10") (pinfunction "Buffer_input_10") (pintype "input"))
      (node (ref "U14") (pin "12") (pinfunction "Output_12") (pintype "input"))
    )
    (net (code "13") (name "Net-(C32-Pad2)") (class "Default")
      (node (ref "C32") (pin "2") (pinfunction "2_2") (pintype "unspecified"))
      (node (ref "R104") (pin "2") (pinfunction "2_2") (pintype "input"))
    )
    (net (code "14") (name "Net-(C38-Pad2)") (class "Default")
      (node (ref "C38") (pin "2") (pinfunction "2_2") (pintype "input"))
      (node (ref "R94") (pin "1") (pinfunction "1_1") (pintype "input"))
    )
    (net (code "15") (name "Net-(C44-Pad2)") (class "Default")
      (node (ref "C44") (pin "2") (pinfunction "2_2") (pintype "unspecified"))
      (node (ref "R101") (pin "1") (pinfunction "1_1") (pintype "input"))
      (node (ref "R96") (pin "1") (pinfunction "1_1") (pintype "input"))
    )
    (net (code "16") (name "Net-(D14-A)") (class "Default")
      (node (ref "D14") (pin "2") (pinfunction "A_2") (pintype "input"))
      (node (ref "D15") (pin "1") (pinfunction "K_1") (pintype "input"))
      (node (ref "U21") (pin "1") (pinfunction "OUT1_1") (pintype "output"))
    )
    (net (code "17") (name "Net-(D14-K)") (class "Default")
      (node (ref "D14") (pin "1") (pinfunction "K_1") (pintype "input"))
      (node (ref "R96") (pin "2") (pinfunction "2_2") (pintype "input"))
      (node (ref "R97") (pin "1") (pinfunction "1_1") (pintype "input"))
      (node (ref "U21") (pin "2") (pinfunction "IN1-_2") (pintype "unspecified"))
    )
    (net (code "18") (name "Net-(D15-A)") (class "Default")
      (node (ref "D15") (pin "2") (pinfunction "A_2") (pintype "input"))
      (node (ref "R97") (pin "2") (pinfunction "2_2") (pintype "input"))
      (node (ref "R98") (pin "1") (pinfunction "1_1") (pintype "input"))
    )
    (net (code "19") (name "Net-(D16-A)") (class "Default")
      (node (ref "D16") (pin "2") (pinfunction "A_2") (pintype "input"))
      (node (ref "R100") (pin "1") (pinfunction "1_1") (pintype "input"))
    )
    (net (code "20") (name "Net-(Q1-E)") (class "Default")
      (node (ref "Q1") (pin "2") (pinfunction "E_2") (pintype "unspecified"))
      (node (ref "Q2") (pin "1") (pinfunction "B_1") (pintype "unspecified"))
    )
    (net (code "21") (name "Net-(Q2-E)") (class "Default")
      (node (ref "Q2") (pin "2") (pinfunction "E_2") (pintype "unspecified"))
      (node (ref "R90") (pin "2") (pinfunction "2_2") (pintype "input"))
    )
    (net (code "22") (name "Net-(R81-Pad1)") (class "Default")
      (node (ref "R81") (pin "1") (pinfunction "1_1") (pintype "input"))
      (node (ref "R85") (pin "2") (pinfunction "2_2") (pintype "input"))
      (node (ref "R89") (pin "1") (pinfunction "1_1") (pintype "input"))
      (node (ref "U14") (pin "4") (pinfunction "Input-_4") (pintype "input"))
    )
    (net (code "23") (name "Net-(R83-Pad2)") (class "Default")
      (node (ref "R83") (pin "2") (pinfunction "2_2") (pintype "input"))
      (node (ref "R84") (pin "1") (pinfunction "1_1") (pintype "input"))
      (node (ref "U14") (pin "8") (pinfunction "Buffer_output_8") (pintype "input"))
      (node (ref "VR2") (pin "1") (pinfunction "1_1") (pintype "input"))
    )
    (net (code "24") (name "Net-(R84-Pad2)") (class "Default")
      (node (ref "R84") (pin "2") (pinfunction "2_2") (pintype "input"))
      (node (ref "R86") (pin "1") (pinfunction "1_1") (pintype "input"))
      (node (ref "U14") (pin "14") (pinfunction "Input+_14") (pintype "input"))
    )
    (net (code "25") (name "Net-(R85-Pad1)") (class "Default")
      (node (ref "R85") (pin "1") (pinfunction "1_1") (pintype "input"))
      (node (ref "VR2") (pin "2") (pinfunction "2_2") (pintype "input"))
      (node (ref "VR2") (pin "3") (pinfunction "3_3") (pintype "input"))
    )
    (net (code "26") (name "Net-(R87-Pad1)") (class "Default")
      (node (ref "R87") (pin "1") (pinfunction "1_1") (pintype "input"))
      (node (ref "U14") (pin "13") (pinfunction "Input-_13") (pintype "input"))
    )
    (net (code "27") (name "Net-(R90-Pad1)") (class "Default")
      (node (ref "R90") (pin "1") (pinfunction "1_1") (pintype "input"))
      (node (ref "R91") (pin "1") (pinfunction "1_1") (pintype "input"))
      (node (ref "U14") (pin "1") (pinfunction "Amp_bias_input_1") (pintype "input"))
      (node (ref "U14") (pin "16") (pinfunction "Amp_bias_input_16") (pintype "input"))
    )
    (net (code "28") (name "Net-(R91-Pad2)") (class "Default")
      (node (ref "R91") (pin "2") (pinfunction "2_2") (pintype "input"))
      (node (ref "VR5") (pin "1") (pinfunction "1_1") (pintype "input"))
    )
    (net (code "29") (name "Net-(R102-Pad2)") (class "Default")
      (node (ref "R102") (pin "2") (pinfunction "2_2") (pintype "input"))
      (node (ref "VR3") (pin "1") (pinfunction "1_1") (pintype "input"))
    )
    (net (code "30") (name "Net-(R104-Pad1)") (class "Default")
      (node (ref "R104") (pin "1") (pinfunction "1_1") (pintype "input"))
      (node (ref "R82") (pin "1") (pinfunction "1_1") (pintype "input"))
      (node (ref "U14") (pin "3") (pinfunction "Input+_3") (pintype "input"))
    )
    (net (code "31") (name "Net-(U11-A)") (class "Default")
      (node (ref "R103") (pin "1") (pinfunction "1_1") (pintype "input"))
      (node (ref "U11") (pin "1") (pinfunction "A_1") (pintype "unspecified"))
    )
    (net (code "32") (name "Net-(U11-K)") (class "Default")
      (node (ref "U11") (pin "2") (pinfunction "K_2") (pintype "unspecified"))
      (node (ref "U26") (pin "3") (pinfunction "3_3") (pintype "unspecified"))
    )
    (net (code "33") (name "Net-(U20A-IN1+)") (class "Default")
      (node (ref "C48") (pin "1") (pinfunction "1_1") (pintype "input"))
      (node (ref "R105") (pin "1") (pinfunction "1_1") (pintype "input"))
      (node (ref "R106") (pin "2") (pinfunction "2_2") (pintype "input"))
      (node (ref "U20") (pin "3") (pinfunction "IN1+_3") (pintype "unspecified"))
    )
    (net (code "34") (name "Net-(U20B-IN2-)") (class "Default")
      (node (ref "R94") (pin "2") (pinfunction "2_2") (pintype "input"))
      (node (ref "U20") (pin "6") (pinfunction "IN2-_6") (pintype "unspecified"))
      (node (ref "VR6") (pin "1") (pinfunction "1_1") (pintype "input"))
    )
    (net (code "35") (name "Net-(U20B-OUT2)") (class "Default")
      (node (ref "C44") (pin "1") (pinfunction "1_1") (pintype "unspecified"))
      (node (ref "U20") (pin "7") (pinfunction "OUT2_7") (pintype "output"))
      (node (ref "VR6") (pin "2") (pinfunction "2_2") (pintype "input"))
      (node (ref "VR6") (pin "3") (pinfunction "3_3") (pintype "input"))
    )
    (net (code "36") (name "Net-(U21B-IN2-)") (class "Default")
      (node (ref "C45") (pin "1") (pinfunction "1_1") (pintype "unspecified"))
      (node (ref "R101") (pin "2") (pinfunction "2_2") (pintype "input"))
      (node (ref "R95") (pin "1") (pinfunction "1_1") (pintype "input"))
      (node (ref "R98") (pin "2") (pinfunction "2_2") (pintype "input"))
      (node (ref "R99") (pin "1") (pinfunction "1_1") (pintype "input"))
      (node (ref "U21") (pin "6") (pinfunction "IN2-_6") (pintype "unspecified"))
    )
    (net (code "37") (name "Net-(U21B-OUT2)") (class "Default")
      (node (ref "C45") (pin "2") (pinfunction "2_2") (pintype "unspecified"))
      (node (ref "R100") (pin "2") (pinfunction "2_2") (pintype "input"))
      (node (ref "R95") (pin "2") (pinfunction "2_2") (pintype "input"))
      (node (ref "U21") (pin "7") (pinfunction "OUT2_7") (pintype "output"))
    )
    (net (code "38") (name "Net-(U27A-IN1+)") (class "Default")
      (node (ref "C51") (pin "2") (pinfunction "2_2") (pintype "input"))
      (node (ref "R3") (pin "2") (pinfunction "2_2") (pintype "input"))
      (node (ref "U27") (pin "3") (pinfunction "IN1+_3") (pintype "unspecified"))
    )
    (net (code "39") (name "Net-(U27B-IN2+)") (class "Default")
      (node (ref "U27") (pin "5") (pinfunction "IN2+_5") (pintype "unspecified"))
      (node (ref "VR1") (pin "2") (pinfunction "2_2") (pintype "input"))
    )
    (net (code "40") (name "Net-(U27B-IN2-)") (class "Default")
      (node (ref "C27") (pin "1") (pinfunction "1_1") (pintype "unspecified"))
      (node (ref "U27") (pin "6") (pinfunction "IN2-_6") (pintype "unspecified"))
      (node (ref "U27") (pin "7") (pinfunction "OUT2_7") (pintype "output"))
    )
    (net (code "41") (name "VCC") (class "Default")
      (node (ref "C47") (pin "1") (pinfunction "1_1") (pintype "input"))
      (node (ref "DC1") (pin "2") (pinfunction "2_2") (pintype "unspecified"))
      (node (ref "R103") (pin "2") (pinfunction "2_2") (pintype "input"))
      (node (ref "R105") (pin "2") (pinfunction "2_2") (pintype "input"))
      (node (ref "R99") (pin "2") (pinfunction "2_2") (pintype "input"))
      (node (ref "U14") (pin "11") (pinfunction "V+_11") (pintype "input"))
      (node (ref "U19") (pin "3") (pinfunction "Vin_3") (pintype "unspecified"))
      (node (ref "U20") (pin "8") (pinfunction "VCC+_8") (pintype "unspecified"))
      (node (ref "U21") (pin "8") (pinfunction "VCC+_8") (pintype "unspecified"))
      (node (ref "U27") (pin "8") (pinfunction "VCC+_8") (pintype "unspecified"))
    )
    (net (code "42") (name "VREF") (class "Default")
      (node (ref "C51") (pin "1") (pinfunction "1_1") (pintype "input"))
      (node (ref "R1") (pin "1") (pinfunction "1_1") (pintype "input"))
      (node (ref "R81") (pin "2") (pinfunction "2_2") (pintype "input"))
      (node (ref "R82") (pin "2") (pinfunction "2_2") (pintype "input"))
      (node (ref "R86") (pin "2") (pinfunction "2_2") (pintype "input"))
      (node (ref "R87") (pin "2") (pinfunction "2_2") (pintype "input"))
      (node (ref "U20") (pin "1") (pinfunction "OUT1_1") (pintype "output"))
      (node (ref "U20") (pin "2") (pinfunction "IN1-_2") (pintype "unspecified"))
      (node (ref "U20") (pin "5") (pinfunction "IN2+_5") (pintype "unspecified"))
      (node (ref "U21") (pin "3") (pinfunction "IN1+_3") (pintype "unspecified"))
      (node (ref "U21") (pin "5") (pinfunction "IN2+_5") (pintype "unspecified"))
    )
    (net (code "43") (name "unconnected-(DC1-Pad3)") (class "Default")
      (node (ref "DC1") (pin "3") (pinfunction "3_3") (pintype "unspecified+no_connect"))
    )
    (net (code "44") (name "unconnected-(U14-Diode_bias-Pad2)") (class "Default")
      (node (ref "U14") (pin "2") (pinfunction "Diode_bias_2") (pintype "input"))
    )
    (net (code "45") (name "unconnected-(U14-Diode_bias-Pad15)") (class "Default")
      (node (ref "U14") (pin "15") (pinfunction "Diode_bias_15") (pintype "input"))
    )
  )
)
